# GPRS.net
KiCad netlist of a schematic drawn in Altium Designer
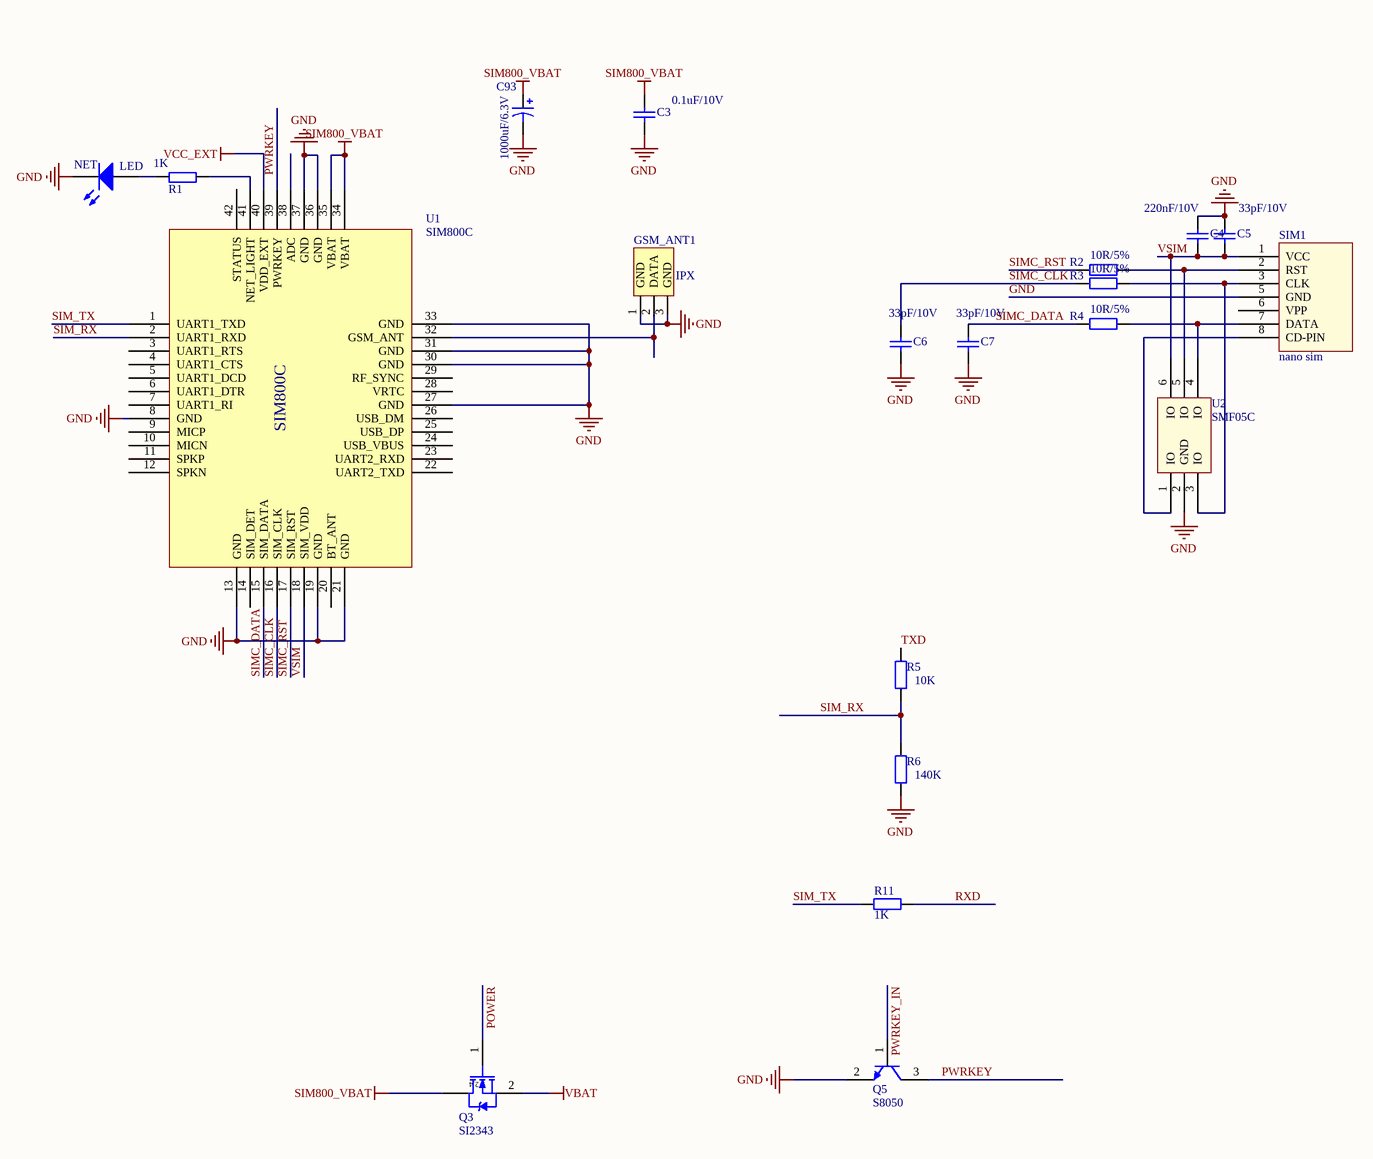
[diagram p0: GPRS.SchDoc]

(export (version "E")
  (design (tool "Eeschema 10.0.6"))
  (components
    (comp (ref "C3")
      (value "0.1uF/10V")
      (footprint "0603C")
      (description "Capacitor")
      (fields (field (name "PUBLISHER") "Altium Limited"))
      (libsource (lib "Miscellaneous Devices") (part "Cap"))
    )
    (comp (ref "C4")
      (value "220nF/10V")
      (footprint "0603C")
      (description "Capacitor")
      (fields (field (name "PUBLISHER") "Altium Limited"))
      (libsource (lib "Miscellaneous Devices") (part "Cap"))
    )
    (comp (ref "C5")
      (value "33pF/10V")
      (footprint "0603C")
      (description "Capacitor")
      (fields (field (name "PUBLISHER") "Altium Limited"))
      (libsource (lib "Miscellaneous Devices") (part "Cap"))
    )
    (comp (ref "C6")
      (value "33pF/10V")
      (footprint "0603C")
      (description "Capacitor")
      (fields (field (name "PUBLISHER") "Altium Limited"))
      (libsource (lib "Miscellaneous Devices") (part "Cap"))
    )
    (comp (ref "C7")
      (value "33pF/10V")
      (footprint "0603C")
      (description "Capacitor")
      (fields (field (name "PUBLISHER") "Altium Limited"))
      (libsource (lib "Miscellaneous Devices") (part "Cap"))
    )
    (comp (ref "C93")
      (value "1000uF/6.3V")
      (footprint "7343")
      (description "Polarized Capacitor (Radial)")
      (fields (field (name "PUBLISHER") "Altium Limited"))
      (libsource (lib "Miscellaneous Devices") (part "Cap Pol1"))
    )
    (comp (ref "GSM_ANT1")
      (value "IPX")
      (footprint "IPX")
      (description "IPEX座")
      (libsource (lib "SIM800C 原理图库") (part "IPEX"))
    )
    (comp (ref "NET")
      (value "LED")
      (footprint "0603LED")
      (description "Typical RED, GREEN, YELLOW, AMBER GaAs LED")
      (fields (field (name "PUBLISHER") "Altium Limited"))
      (libsource (lib "SIM800C 原理图库") (part "LED2"))
    )
    (comp (ref "Q3")
      (value "SI2343")
      (footprint "SOT23-3")
      (description "BUK92150-55A")
      (fields (field (name "PUBLISHER") "Altium Limited"))
      (libsource (lib "Schlib1") (part "BUK92150-55A"))
    )
    (comp (ref "Q5") (value "S8050") (footprint "SOT23-3") (libsource (lib "Schlib1") (part "NPN")))
    (comp (ref "R1") (value "1K") (footprint "0603r") (libsource (lib "SIM800C 原理图库") (part "R")))
    (comp (ref "R2")
      (value "10R/5%")
      (footprint "0603R")
      (description "Resistor")
      (fields (field (name "PUBLISHER") "Altium Limited"))
      (libsource (lib "") (part "Res2_2"))
    )
    (comp (ref "R3")
      (value "10R/5%")
      (footprint "0603R")
      (description "Resistor")
      (fields (field (name "PUBLISHER") "Altium Limited"))
      (libsource (lib "") (part "Res2_2"))
    )
    (comp (ref "R4")
      (value "10R/5%")
      (footprint "0603R")
      (description "Resistor")
      (fields (field (name "PUBLISHER") "Altium Limited"))
      (libsource (lib "") (part "Res2_2"))
    )
    (comp (ref "R5")
      (value "10K")
      (footprint "0603R")
      (description "Resistor")
      (fields (field (name "PUBLISHER") "Altium Limited"))
      (libsource (lib "") (part "Res2_1"))
    )
    (comp (ref "R6")
      (value "140K")
      (footprint "0603R")
      (description "Resistor")
      (fields (field (name "PUBLISHER") "Altium Limited"))
      (libsource (lib "") (part "Res2_1"))
    )
    (comp (ref "R11")
      (value "1K")
      (footprint "0603R")
      (description "Resistor")
      (fields (field (name "PUBLISHER") "Altium Limited"))
      (libsource (lib "Miscellaneous Devices") (part "Res2"))
    )
    (comp (ref "SIM1") (value "nano sim") (footprint "Nano SIM") (libsource (lib "lm") (part "nano sim")))
    (comp (ref "U1")
      (value "SIM800C")
      (footprint "SIM800C")
      (libsource (lib "SIM800C 原理图库") (part "SIM800C"))
    )
    (comp (ref "U2") (value "SMF05C") (footprint "SC70-6L") (libsource (lib "lm") (part "SMF05C")))
  )
  (nets
    (net (code "1") (name "/POWER") (class "Default")
      (node (ref "Q3") (pin "1") (pinfunction "G_1") (pintype "passive"))
    )
    (net (code "2") (name "/PWRKEY") (class "Default")
      (node (ref "Q5") (pin "3") (pinfunction "C_3") (pintype "passive"))
      (node (ref "U1") (pin "39") (pinfunction "PWRKEY_39") (pintype "passive"))
    )
    (net (code "3") (name "/PWRKEY_IN") (class "Default")
      (node (ref "Q5") (pin "1") (pinfunction "B_1") (pintype "passive"))
    )
    (net (code "4") (name "/RXD") (class "Default")
      (node (ref "R11") (pin "2") (pinfunction "2_2") (pintype "passive"))
    )
    (net (code "5") (name "/SIMC_CLK") (class "Default")
      (node (ref "C6") (pin "1") (pinfunction "1_1") (pintype "passive"))
      (node (ref "R3") (pin "2") (pinfunction "2_2") (pintype "passive"))
      (node (ref "U1") (pin "16") (pinfunction "SIM_CLK_16") (pintype "passive"))
    )
    (net (code "6") (name "/SIMC_DATA") (class "Default")
      (node (ref "C7") (pin "1") (pinfunction "1_1") (pintype "passive"))
      (node (ref "R4") (pin "2") (pinfunction "2_2") (pintype "passive"))
      (node (ref "U1") (pin "15") (pinfunction "SIM_DATA_15") (pintype "passive"))
    )
    (net (code "7") (name "/SIMC_RST") (class "Default")
      (node (ref "R2") (pin "2") (pinfunction "2_2") (pintype "passive"))
      (node (ref "U1") (pin "17") (pinfunction "SIM_RST_17") (pintype "passive"))
    )
    (net (code "8") (name "/SIM_RX") (class "Default")
      (node (ref "R5") (pin "2") (pinfunction "2_2") (pintype "passive"))
      (node (ref "R6") (pin "1") (pinfunction "1_1") (pintype "passive"))
      (node (ref "U1") (pin "2") (pinfunction "UART1_RXD_2") (pintype "passive"))
    )
    (net (code "9") (name "/SIM_TX") (class "Default")
      (node (ref "R11") (pin "1") (pinfunction "1_1") (pintype "passive"))
      (node (ref "U1") (pin "1") (pinfunction "UART1_TXD_1") (pintype "passive"))
    )
    (net (code "10") (name "/TXD") (class "Default")
      (node (ref "R5") (pin "1") (pinfunction "1_1") (pintype "passive"))
    )
    (net (code "11") (name "/VSIM") (class "Default")
      (node (ref "C4") (pin "2") (pinfunction "2_2") (pintype "passive"))
      (node (ref "C5") (pin "2") (pinfunction "2_2") (pintype "passive"))
      (node (ref "SIM1") (pin "1") (pinfunction "VCC_1") (pintype "passive"))
      (node (ref "U1") (pin "18") (pinfunction "SIM_VDD_18") (pintype "passive"))
      (node (ref "U2") (pin "6") (pinfunction "IO_6") (pintype "passive"))
    )
    (net (code "12") (name "GND") (class "Default")
      (node (ref "C3") (pin "2") (pinfunction "2_2") (pintype "passive"))
      (node (ref "C4") (pin "1") (pinfunction "1_1") (pintype "passive"))
      (node (ref "C5") (pin "1") (pinfunction "1_1") (pintype "passive"))
      (node (ref "C6") (pin "2") (pinfunction "2_2") (pintype "passive"))
      (node (ref "C7") (pin "2") (pinfunction "2_2") (pintype "passive"))
      (node (ref "C93") (pin "2") (pinfunction "2_2") (pintype "passive"))
      (node (ref "GSM_ANT1") (pin "1") (pinfunction "GND_1") (pintype "passive"))
      (node (ref "GSM_ANT1") (pin "3") (pinfunction "GND_3") (pintype "passive"))
      (node (ref "NET") (pin "2") (pinfunction "K_2") (pintype "passive"))
      (node (ref "Q5") (pin "2") (pinfunction "E_2") (pintype "passive"))
      (node (ref "R6") (pin "2") (pinfunction "2_2") (pintype "passive"))
      (node (ref "SIM1") (pin "5") (pinfunction "GND_5") (pintype "passive"))
      (node (ref "U1") (pin "13") (pinfunction "GND_13") (pintype "passive"))
      (node (ref "U1") (pin "19") (pinfunction "GND_19") (pintype "passive"))
      (node (ref "U1") (pin "21") (pinfunction "GND_21") (pintype "passive"))
      (node (ref "U1") (pin "27") (pinfunction "GND_27") (pintype "passive"))
      (node (ref "U1") (pin "30") (pinfunction "GND_30") (pintype "passive"))
      (node (ref "U1") (pin "31") (pinfunction "GND_31") (pintype "passive"))
      (node (ref "U1") (pin "33") (pinfunction "GND_33") (pintype "passive"))
      (node (ref "U1") (pin "36") (pinfunction "GND_36") (pintype "passive"))
      (node (ref "U1") (pin "37") (pinfunction "GND_37") (pintype "passive"))
      (node (ref "U1") (pin "8") (pinfunction "GND_8") (pintype "passive"))
      (node (ref "U2") (pin "2") (pinfunction "GND_2") (pintype "passive"))
    )
    (net (code "13") (name "Net-(GSM_ANT1-DATA)") (class "Default")
      (node (ref "GSM_ANT1") (pin "2") (pinfunction "DATA_2") (pintype "passive"))
      (node (ref "U1") (pin "32") (pinfunction "GSM_ANT_32") (pintype "passive"))
    )
    (net (code "14") (name "Net-(NET-A)") (class "Default")
      (node (ref "NET") (pin "1") (pinfunction "A_1") (pintype "passive"))
      (node (ref "R1") (pin "1") (pintype "passive"))
    )
    (net (code "15") (name "Net-(SIM1-CD-PIN)") (class "Default")
      (node (ref "SIM1") (pin "8") (pinfunction "CD-PIN_8") (pintype "passive"))
      (node (ref "U2") (pin "1") (pinfunction "IO_1") (pintype "passive"))
    )
    (net (code "16") (name "Net-(SIM1-CLK)") (class "Default")
      (node (ref "R3") (pin "1") (pinfunction "1_1") (pintype "passive"))
      (node (ref "SIM1") (pin "3") (pinfunction "CLK_3") (pintype "passive"))
      (node (ref "U2") (pin "3") (pinfunction "IO_3") (pintype "passive"))
    )
    (net (code "17") (name "Net-(SIM1-DATA)") (class "Default")
      (node (ref "R4") (pin "1") (pinfunction "1_1") (pintype "passive"))
      (node (ref "SIM1") (pin "7") (pinfunction "DATA_7") (pintype "passive"))
      (node (ref "U2") (pin "4") (pinfunction "IO_4") (pintype "passive"))
    )
    (net (code "18") (name "Net-(SIM1-RST)") (class "Default")
      (node (ref "R2") (pin "1") (pinfunction "1_1") (pintype "passive"))
      (node (ref "SIM1") (pin "2") (pinfunction "RST_2") (pintype "passive"))
      (node (ref "U2") (pin "5") (pinfunction "IO_5") (pintype "passive"))
    )
    (net (code "19") (name "Net-(U1-NET_LIGHT)") (class "Default")
      (node (ref "R1") (pin "2") (pintype "passive"))
      (node (ref "U1") (pin "41") (pinfunction "NET_LIGHT_41") (pintype "passive"))
    )
    (net (code "20") (name "SIM800_VBAT") (class "Default")
      (node (ref "C3") (pin "1") (pinfunction "1_1") (pintype "passive"))
      (node (ref "C93") (pin "1") (pinfunction "1_1") (pintype "passive"))
      (node (ref "Q3") (pin "3") (pinfunction "D_3") (pintype "passive"))
      (node (ref "U1") (pin "34") (pinfunction "VBAT_34") (pintype "passive"))
      (node (ref "U1") (pin "35") (pinfunction "VBAT_35") (pintype "passive"))
    )
    (net (code "21") (name "VBAT") (class "Default")
      (node (ref "Q3") (pin "2") (pinfunction "S_2") (pintype "passive"))
    )
    (net (code "22") (name "VCC_EXT") (class "Default")
      (node (ref "U1") (pin "40") (pinfunction "VDD_EXT_40") (pintype "passive"))
    )
    (net (code "23") (name "unconnected-(SIM1-VPP-Pad6)") (class "Default")
      (node (ref "SIM1") (pin "6") (pinfunction "VPP_6") (pintype "passive"))
    )
    (net (code "24") (name "unconnected-(U1-ADC-Pad38)") (class "Default")
      (node (ref "U1") (pin "38") (pinfunction "ADC_38") (pintype "passive"))
    )
    (net (code "25") (name "unconnected-(U1-BT_ANT-Pad20)") (class "Default")
      (node (ref "U1") (pin "20") (pinfunction "BT_ANT_20") (pintype "passive"))
    )
    (net (code "26") (name "unconnected-(U1-MICN-Pad10)") (class "Default")
      (node (ref "U1") (pin "10") (pinfunction "MICN_10") (pintype "passive"))
    )
    (net (code "27") (name "unconnected-(U1-MICP-Pad9)") (class "Default")
      (node (ref "U1") (pin "9") (pinfunction "MICP_9") (pintype "passive"))
    )
    (net (code "28") (name "unconnected-(U1-RF_SYNC-Pad29)") (class "Default")
      (node (ref "U1") (pin "29") (pinfunction "RF_SYNC_29") (pintype "passive"))
    )
    (net (code "29") (name "unconnected-(U1-SIM_DET-Pad14)") (class "Default")
      (node (ref "U1") (pin "14") (pinfunction "SIM_DET_14") (pintype "passive"))
    )
    (net (code "30") (name "unconnected-(U1-SPKN-Pad12)") (class "Default")
      (node (ref "U1") (pin "12") (pinfunction "SPKN_12") (pintype "passive"))
    )
    (net (code "31") (name "unconnected-(U1-SPKP-Pad11)") (class "Default")
      (node (ref "U1") (pin "11") (pinfunction "SPKP_11") (pintype "passive"))
    )
    (net (code "32") (name "unconnected-(U1-STATUS-Pad42)") (class "Default")
      (node (ref "U1") (pin "42") (pinfunction "STATUS_42") (pintype "passive"))
    )
    (net (code "33") (name "unconnected-(U1-UART1_CTS-Pad4)") (class "Default")
      (node (ref "U1") (pin "4") (pinfunction "UART1_CTS_4") (pintype "passive"))
    )
    (net (code "34") (name "unconnected-(U1-UART1_DCD-Pad5)") (class "Default")
      (node (ref "U1") (pin "5") (pinfunction "UART1_DCD_5") (pintype "passive"))
    )
    (net (code "35") (name "unconnected-(U1-UART1_DTR-Pad6)") (class "Default")
      (node (ref "U1") (pin "6") (pinfunction "UART1_DTR_6") (pintype "passive"))
    )
    (net (code "36") (name "unconnected-(U1-UART1_RI-Pad7)") (class "Default")
      (node (ref "U1") (pin "7") (pinfunction "UART1_RI_7") (pintype "passive"))
    )
    (net (code "37") (name "unconnected-(U1-UART1_RTS-Pad3)") (class "Default")
      (node (ref "U1") (pin "3") (pinfunction "UART1_RTS_3") (pintype "passive"))
    )
    (net (code "38") (name "unconnected-(U1-UART2_RXD-Pad23)") (class "Default")
      (node (ref "U1") (pin "23") (pinfunction "UART2_RXD_23") (pintype "passive"))
    )
    (net (code "39") (name "unconnected-(U1-UART2_TXD-Pad22)") (class "Default")
      (node (ref "U1") (pin "22") (pinfunction "UART2_TXD_22") (pintype "passive"))
    )
    (net (code "40") (name "unconnected-(U1-USB_DM-Pad26)") (class "Default")
      (node (ref "U1") (pin "26") (pinfunction "USB_DM_26") (pintype "passive"))
    )
    (net (code "41") (name "unconnected-(U1-USB_DP-Pad25)") (class "Default")
      (node (ref "U1") (pin "25") (pinfunction "USB_DP_25") (pintype "passive"))
    )
    (net (code "42") (name "unconnected-(U1-USB_VBUS-Pad24)") (class "Default")
      (node (ref "U1") (pin "24") (pinfunction "USB_VBUS_24") (pintype "passive"))
    )
    (net (code "43") (name "unconnected-(U1-VRTC-Pad28)") (class "Default")
      (node (ref "U1") (pin "28") (pinfunction "VRTC_28") (pintype "passive"))
    )
  )
)
